# base.net
KiCad netlist of a schematic drawn in EAGLE
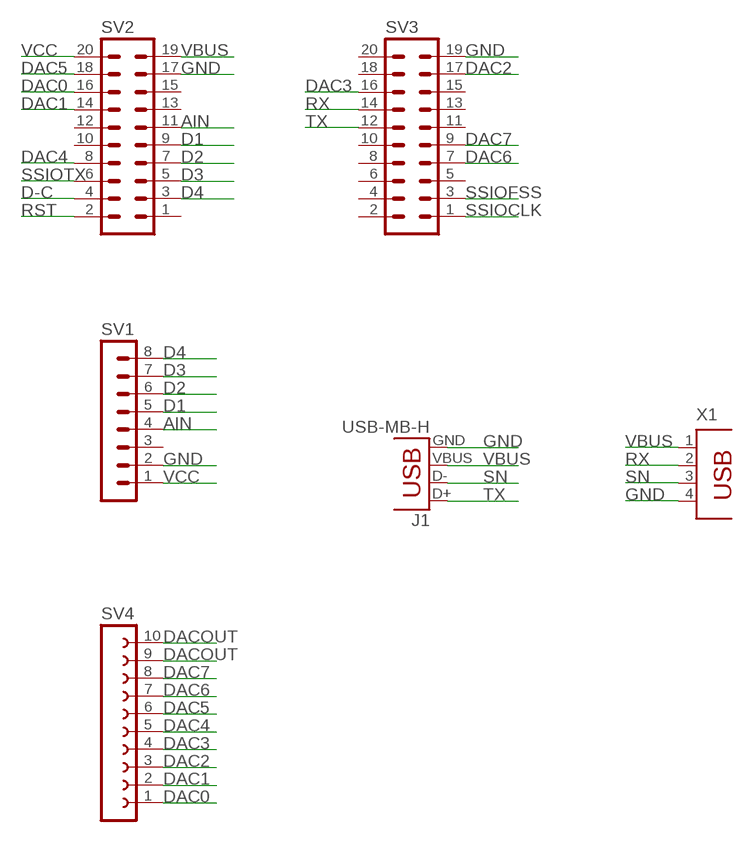
[diagram p0: schematic, sheet 1]

(export (version "E")
  (design (tool "Eeschema 10.0.6"))
  (components
    (comp (ref "J1")
      (value "USB-MB-H")
      (footprint "eagle-import:USB-MB-H")
      (libsource (lib "eagle-import") (part "USB-MB-H"))
    )
    (comp (ref "SV1")
      (value "MA08-1")
      (footprint "eagle-import:MA08-1")
      (libsource (lib "eagle-import") (part "MA08-1"))
    )
    (comp (ref "SV2")
      (value "MA10-2")
      (footprint "eagle-import:MA10-2")
      (libsource (lib "eagle-import") (part "MA10-2"))
    )
    (comp (ref "SV3")
      (value "MA10-2")
      (footprint "eagle-import:MA10-2")
      (libsource (lib "eagle-import") (part "MA10-2"))
    )
    (comp (ref "SV4")
      (value "FE10-1")
      (footprint "eagle-import:FE10")
      (libsource (lib "eagle-import") (part "FE10-1"))
    )
    (comp (ref "X1")
      (value "PN87520")
      (footprint "eagle-import:PN87520")
      (libsource (lib "eagle-import") (part "PN87520"))
    )
  )
  (nets
    (net (code "1") (name "/AIN") (class "Default")
      (node (ref "SV1") (pin "4") (pinfunction "4_4") (pintype "passive"))
      (node (ref "SV2") (pin "11") (pinfunction "11_11") (pintype "passive"))
    )
    (net (code "2") (name "/D-C") (class "Default")
      (node (ref "SV2") (pin "4") (pinfunction "4_4") (pintype "passive"))
    )
    (net (code "3") (name "/D1") (class "Default")
      (node (ref "SV1") (pin "5") (pinfunction "5_5") (pintype "passive"))
      (node (ref "SV2") (pin "9") (pinfunction "9_9") (pintype "passive"))
    )
    (net (code "4") (name "/D2") (class "Default")
      (node (ref "SV1") (pin "6") (pinfunction "6_6") (pintype "passive"))
      (node (ref "SV2") (pin "7") (pinfunction "7_7") (pintype "passive"))
    )
    (net (code "5") (name "/D3") (class "Default")
      (node (ref "SV1") (pin "7") (pinfunction "7_7") (pintype "passive"))
      (node (ref "SV2") (pin "5") (pinfunction "5_5") (pintype "passive"))
    )
    (net (code "6") (name "/D4") (class "Default")
      (node (ref "SV1") (pin "8") (pinfunction "8_8") (pintype "passive"))
      (node (ref "SV2") (pin "3") (pinfunction "3_3") (pintype "passive"))
    )
    (net (code "7") (name "/DAC0") (class "Default")
      (node (ref "SV2") (pin "16") (pinfunction "16_16") (pintype "passive"))
      (node (ref "SV4") (pin "1") (pinfunction "1_1") (pintype "passive"))
    )
    (net (code "8") (name "/DAC1") (class "Default")
      (node (ref "SV2") (pin "14") (pinfunction "14_14") (pintype "passive"))
      (node (ref "SV4") (pin "2") (pinfunction "2_2") (pintype "passive"))
    )
    (net (code "9") (name "/DAC2") (class "Default")
      (node (ref "SV3") (pin "17") (pinfunction "17_17") (pintype "passive"))
      (node (ref "SV4") (pin "3") (pinfunction "3_3") (pintype "passive"))
    )
    (net (code "10") (name "/DAC3") (class "Default")
      (node (ref "SV3") (pin "16") (pinfunction "16_16") (pintype "passive"))
      (node (ref "SV4") (pin "4") (pinfunction "4_4") (pintype "passive"))
    )
    (net (code "11") (name "/DAC4") (class "Default")
      (node (ref "SV2") (pin "8") (pinfunction "8_8") (pintype "passive"))
      (node (ref "SV4") (pin "5") (pinfunction "5_5") (pintype "passive"))
    )
    (net (code "12") (name "/DAC5") (class "Default")
      (node (ref "SV2") (pin "18") (pinfunction "18_18") (pintype "passive"))
      (node (ref "SV4") (pin "6") (pinfunction "6_6") (pintype "passive"))
    )
    (net (code "13") (name "/DAC6") (class "Default")
      (node (ref "SV3") (pin "7") (pinfunction "7_7") (pintype "passive"))
      (node (ref "SV4") (pin "7") (pinfunction "7_7") (pintype "passive"))
    )
    (net (code "14") (name "/DAC7") (class "Default")
      (node (ref "SV3") (pin "9") (pinfunction "9_9") (pintype "passive"))
      (node (ref "SV4") (pin "8") (pinfunction "8_8") (pintype "passive"))
    )
    (net (code "15") (name "/DACOUT") (class "Default")
      (node (ref "SV4") (pin "10") (pinfunction "10_10") (pintype "passive"))
      (node (ref "SV4") (pin "9") (pinfunction "9_9") (pintype "passive"))
    )
    (net (code "16") (name "/GND") (class "Default")
      (node (ref "J1") (pin "GND") (pinfunction "GND_GND") (pintype "bidirectional"))
      (node (ref "SV1") (pin "2") (pinfunction "2_2") (pintype "passive"))
      (node (ref "SV2") (pin "17") (pinfunction "17_17") (pintype "passive"))
      (node (ref "SV3") (pin "19") (pinfunction "19_19") (pintype "passive"))
      (node (ref "X1") (pin "4") (pinfunction "4_4") (pintype "passive"))
    )
    (net (code "17") (name "/RST") (class "Default")
      (node (ref "SV2") (pin "2") (pinfunction "2_2") (pintype "passive"))
    )
    (net (code "18") (name "/RX") (class "Default")
      (node (ref "SV3") (pin "14") (pinfunction "14_14") (pintype "passive"))
      (node (ref "X1") (pin "2") (pinfunction "2_2") (pintype "passive"))
    )
    (net (code "19") (name "/SN") (class "Default")
      (node (ref "J1") (pin "D-") (pinfunction "D-_D-") (pintype "bidirectional"))
      (node (ref "X1") (pin "3") (pinfunction "3_3") (pintype "passive"))
    )
    (net (code "20") (name "/SSIOCLK") (class "Default")
      (node (ref "SV3") (pin "1") (pinfunction "1_1") (pintype "passive"))
    )
    (net (code "21") (name "/SSIOFSS") (class "Default")
      (node (ref "SV3") (pin "3") (pinfunction "3_3") (pintype "passive"))
    )
    (net (code "22") (name "/SSIOTX") (class "Default")
      (node (ref "SV2") (pin "6") (pinfunction "6_6") (pintype "passive"))
    )
    (net (code "23") (name "/TX") (class "Default")
      (node (ref "J1") (pin "D+") (pinfunction "D+_D+") (pintype "bidirectional"))
      (node (ref "SV3") (pin "12") (pinfunction "12_12") (pintype "passive"))
    )
    (net (code "24") (name "/VBUS") (class "Default")
      (node (ref "J1") (pin "VBUS") (pinfunction "VBUS_VBUS") (pintype "bidirectional"))
      (node (ref "SV2") (pin "19") (pinfunction "19_19") (pintype "passive"))
      (node (ref "X1") (pin "1") (pinfunction "1_1") (pintype "passive"))
    )
    (net (code "25") (name "/VCC") (class "Default")
      (node (ref "SV1") (pin "1") (pinfunction "1_1") (pintype "passive"))
      (node (ref "SV2") (pin "20") (pinfunction "20_20") (pintype "passive"))
    )
    (net (code "26") (name "unconnected-(SV1-Pad3)") (class "Default")
      (node (ref "SV1") (pin "3") (pinfunction "3_3") (pintype "passive"))
    )
    (net (code "27") (name "unconnected-(SV2-Pad1)") (class "Default")
      (node (ref "SV2") (pin "1") (pinfunction "1_1") (pintype "passive"))
    )
    (net (code "28") (name "unconnected-(SV2-Pad10)") (class "Default")
      (node (ref "SV2") (pin "10") (pinfunction "10_10") (pintype "passive"))
    )
    (net (code "29") (name "unconnected-(SV2-Pad12)") (class "Default")
      (node (ref "SV2") (pin "12") (pinfunction "12_12") (pintype "passive"))
    )
    (net (code "30") (name "unconnected-(SV2-Pad13)") (class "Default")
      (node (ref "SV2") (pin "13") (pinfunction "13_13") (pintype "passive"))
    )
    (net (code "31") (name "unconnected-(SV2-Pad15)") (class "Default")
      (node (ref "SV2") (pin "15") (pinfunction "15_15") (pintype "passive"))
    )
    (net (code "32") (name "unconnected-(SV3-Pad2)") (class "Default")
      (node (ref "SV3") (pin "2") (pinfunction "2_2") (pintype "passive"))
    )
    (net (code "33") (name "unconnected-(SV3-Pad4)") (class "Default")
      (node (ref "SV3") (pin "4") (pinfunction "4_4") (pintype "passive"))
    )
    (net (code "34") (name "unconnected-(SV3-Pad5)") (class "Default")
      (node (ref "SV3") (pin "5") (pinfunction "5_5") (pintype "passive"))
    )
    (net (code "35") (name "unconnected-(SV3-Pad6)") (class "Default")
      (node (ref "SV3") (pin "6") (pinfunction "6_6") (pintype "passive"))
    )
    (net (code "36") (name "unconnected-(SV3-Pad8)") (class "Default")
      (node (ref "SV3") (pin "8") (pinfunction "8_8") (pintype "passive"))
    )
    (net (code "37") (name "unconnected-(SV3-Pad10)") (class "Default")
      (node (ref "SV3") (pin "10") (pinfunction "10_10") (pintype "passive"))
    )
    (net (code "38") (name "unconnected-(SV3-Pad11)") (class "Default")
      (node (ref "SV3") (pin "11") (pinfunction "11_11") (pintype "passive"))
    )
    (net (code "39") (name "unconnected-(SV3-Pad13)") (class "Default")
      (node (ref "SV3") (pin "13") (pinfunction "13_13") (pintype "passive"))
    )
    (net (code "40") (name "unconnected-(SV3-Pad15)") (class "Default")
      (node (ref "SV3") (pin "15") (pinfunction "15_15") (pintype "passive"))
    )
    (net (code "41") (name "unconnected-(SV3-Pad18)") (class "Default")
      (node (ref "SV3") (pin "18") (pinfunction "18_18") (pintype "passive"))
    )
    (net (code "42") (name "unconnected-(SV3-Pad20)") (class "Default")
      (node (ref "SV3") (pin "20") (pinfunction "20_20") (pintype "passive"))
    )
  )
)
